# CO2_Sensor_Unit_board.net
KiCad netlist of a schematic drawn in Altium Designer
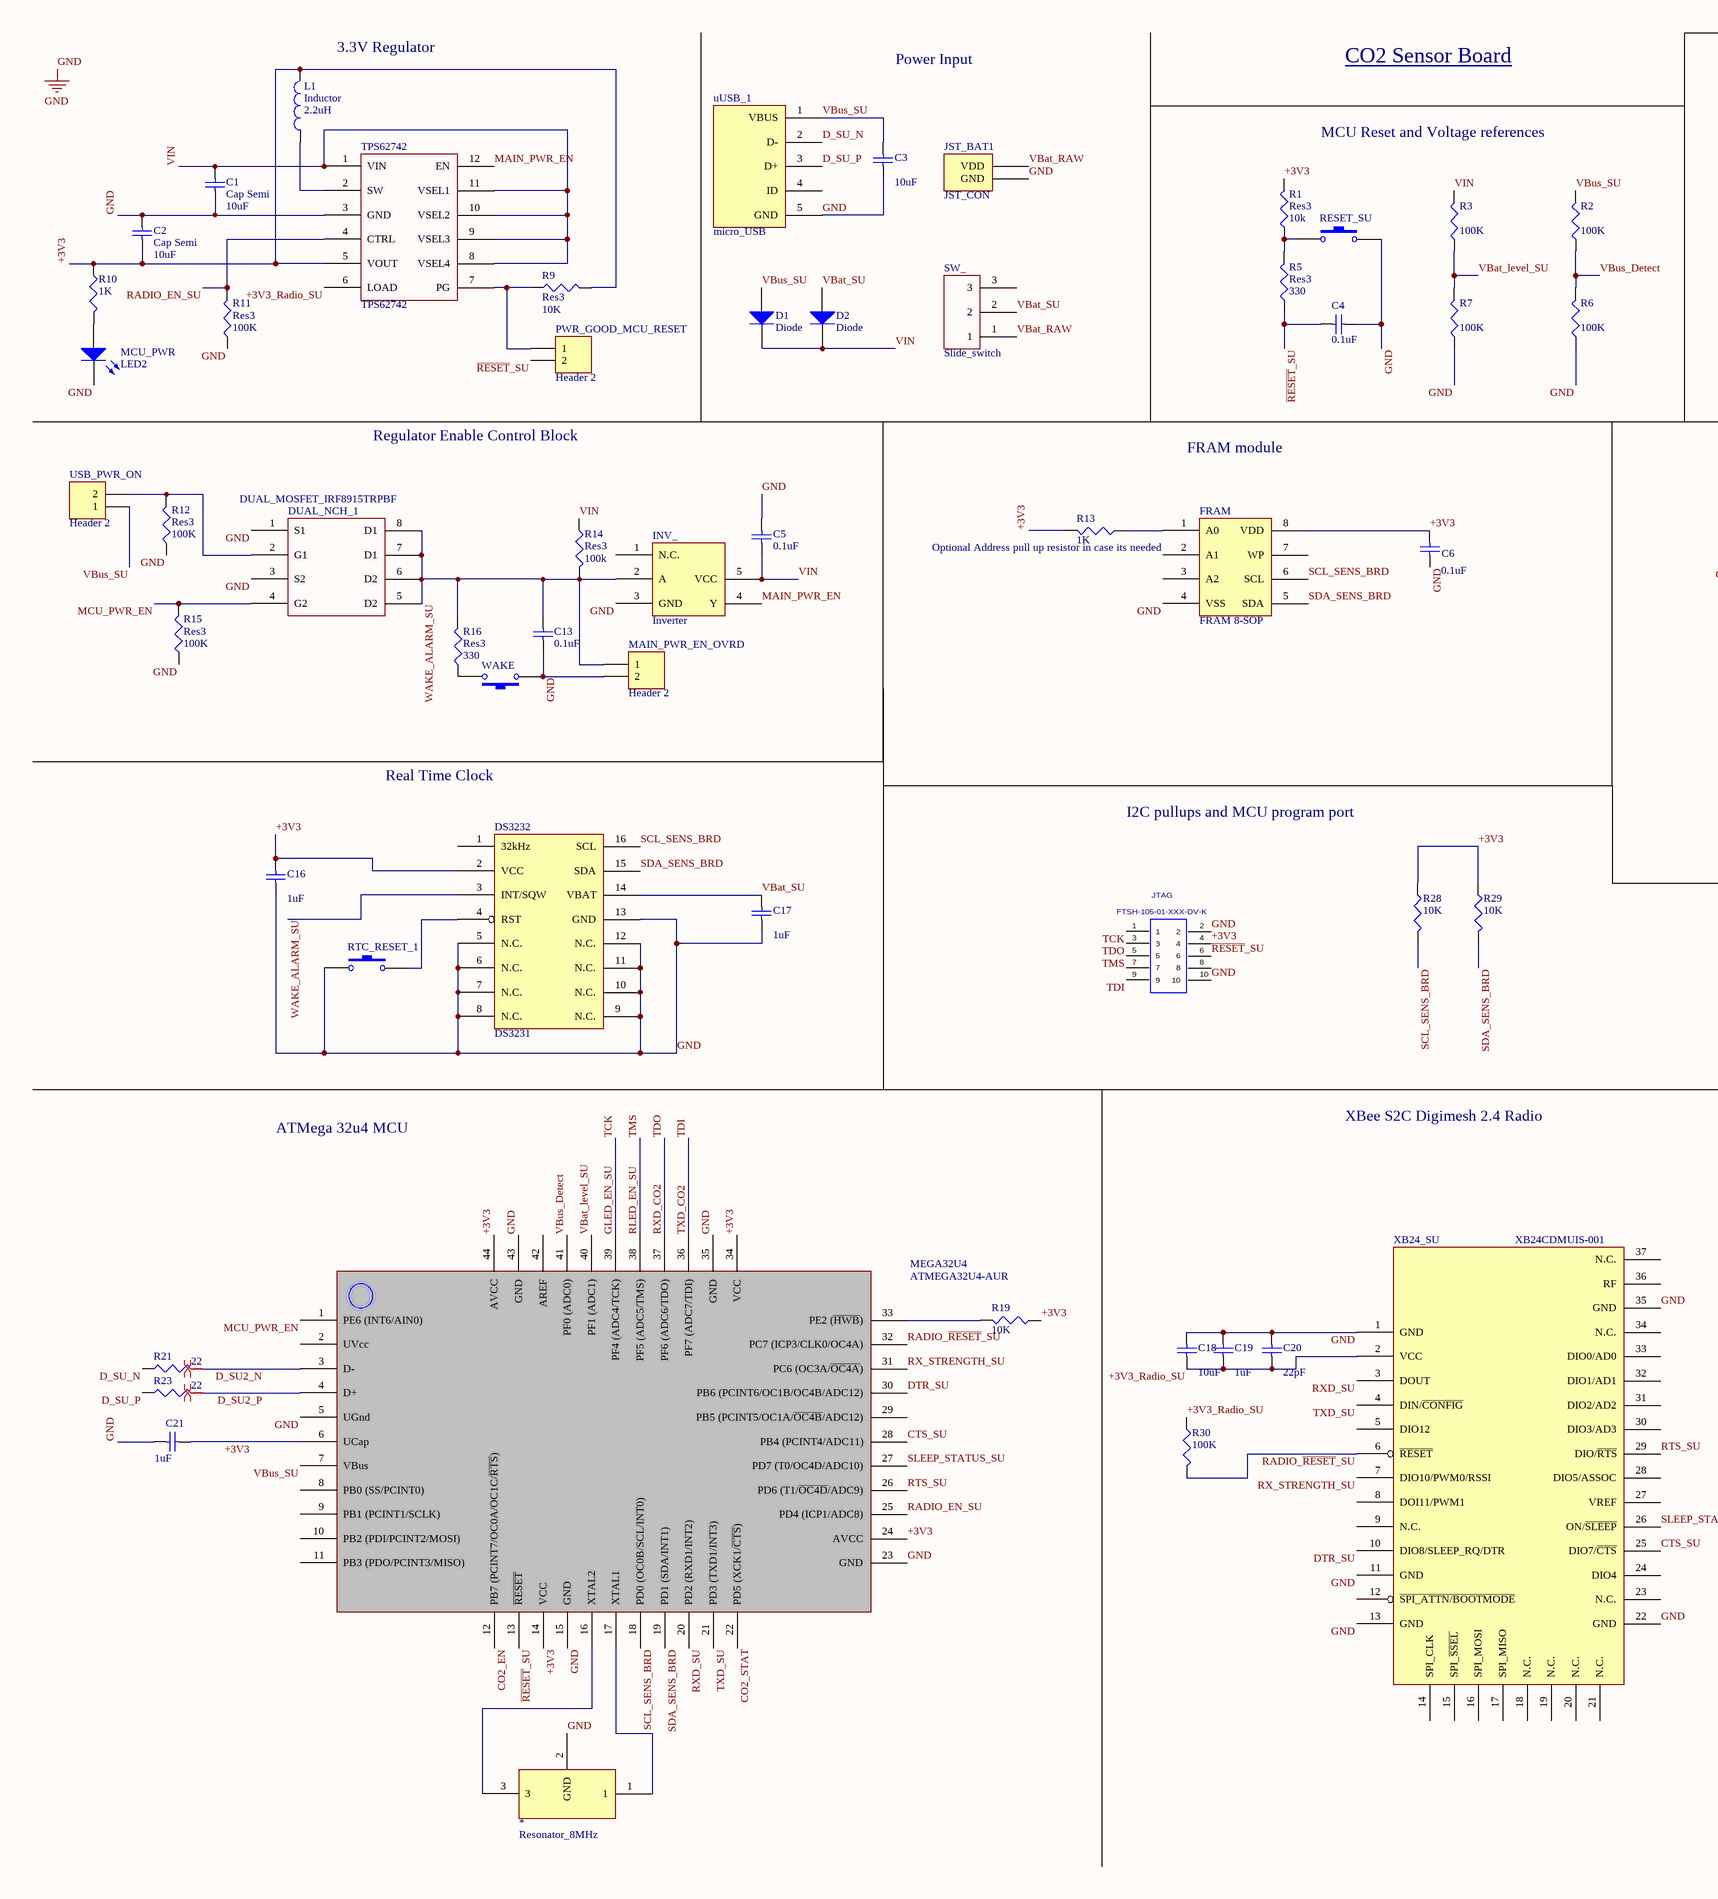
[diagram p0: CO2_Sensor_Unit_board.SchDoc, left]
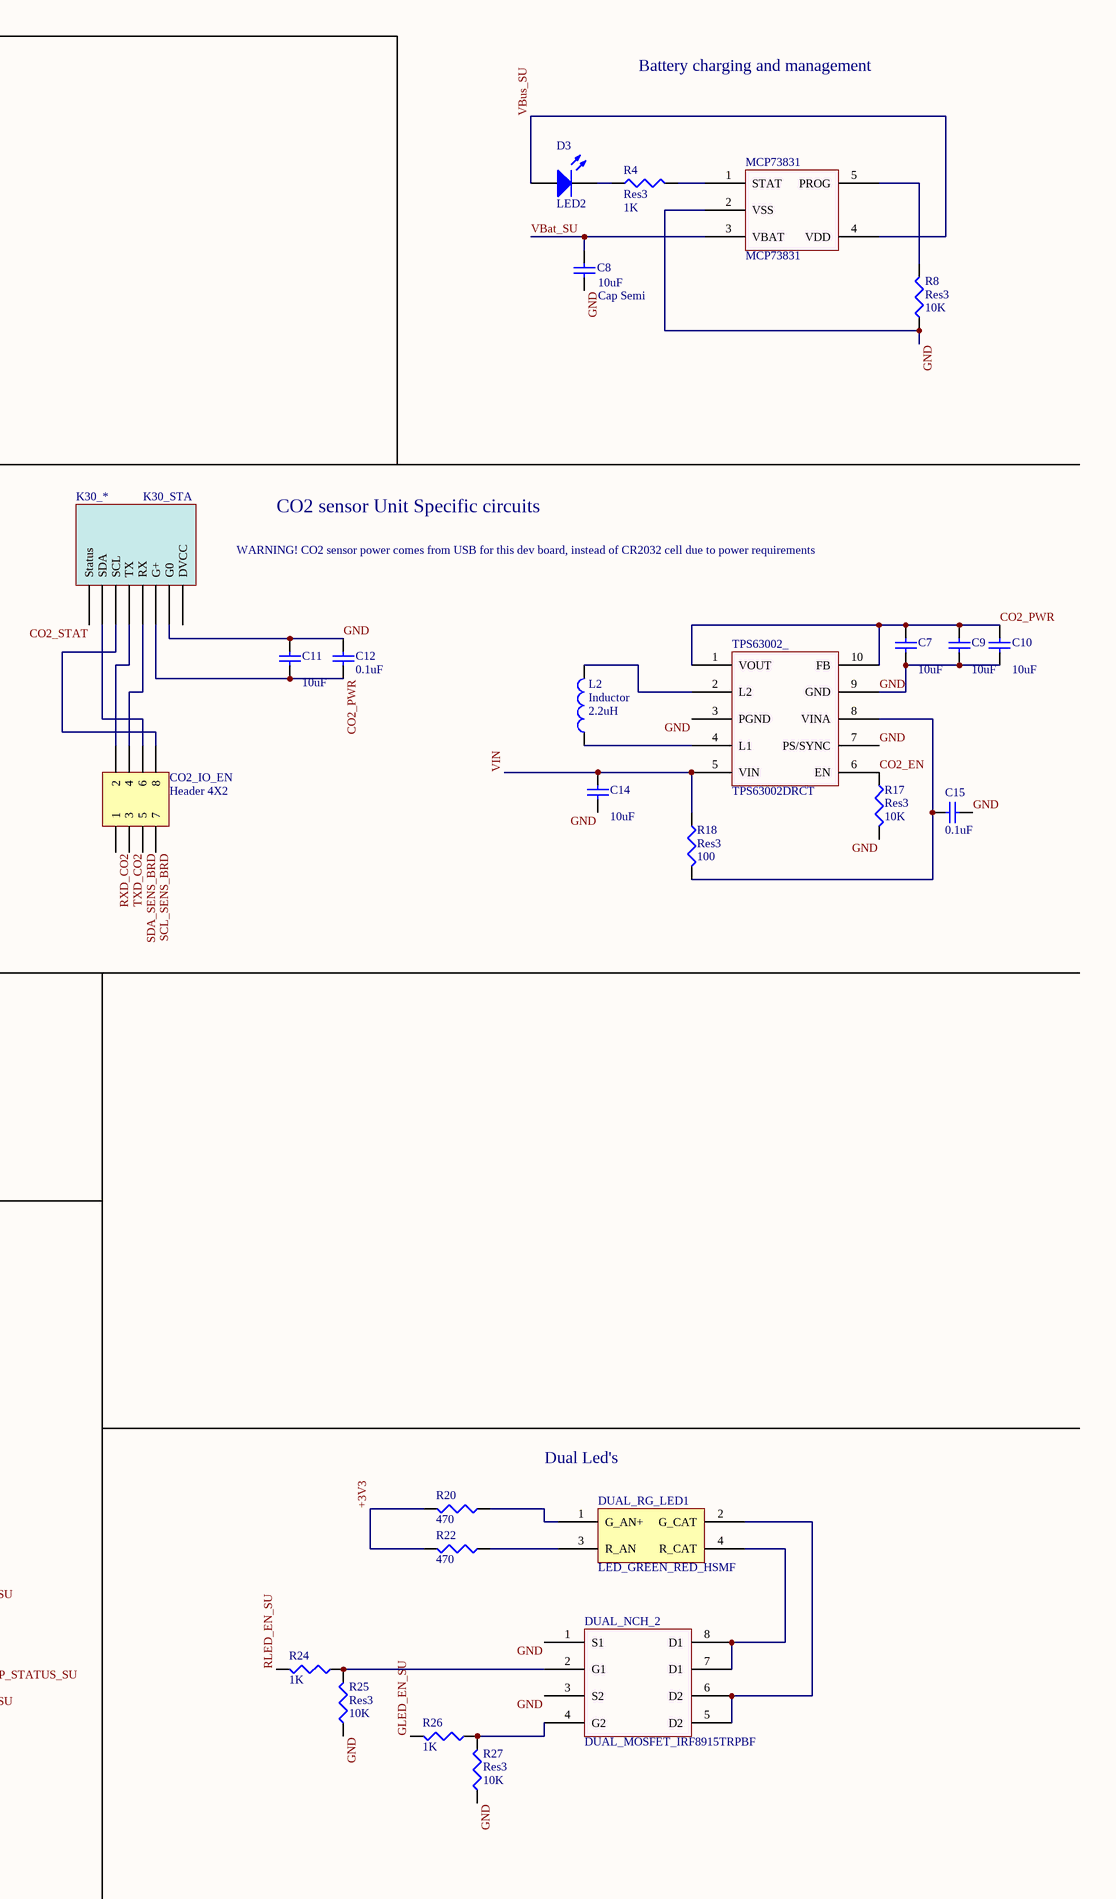
[diagram p1: CO2_Sensor_Unit_board.SchDoc, right]

(export (version "E")
  (design (tool "Eeschema 10.0.6"))
  (components
    (comp (ref "*")
      (value "Resonator_8MHz")
      (footprint "Resonator_8MHz")
      (libsource (lib "SMD_components") (part "Resonator_8MHz"))
    )
    (comp (ref "C1")
      (value "Cap Semi")
      (footprint "1608[0603]")
      (description "Capacitor (Semiconductor SIM Model)")
      (fields (field (name "ALTIUM_VALUE") "10uF") (field (name "PUBLISHER") "Altium Limited"))
      (libsource (lib "Miscellaneous Devices") (part "Cap Semi"))
    )
    (comp (ref "C2")
      (value "Cap Semi")
      (footprint "1608[0603]")
      (description "Capacitor (Semiconductor SIM Model)")
      (fields (field (name "ALTIUM_VALUE") "10uF") (field (name "PUBLISHER") "Altium Limited"))
      (libsource (lib "Miscellaneous Devices") (part "Cap Semi"))
    )
    (comp (ref "C3")
      (value "10uF")
      (footprint "1608[0603]")
      (description "Capacitor (Semiconductor SIM Model)")
      (fields (field (name "Comment") "Cap Semi") (field (name "PUBLISHER") "Altium Limited"))
      (libsource (lib "Miscellaneous Devices") (part "Cap Semi"))
    )
    (comp (ref "C4")
      (value "0.1uF")
      (footprint "C0805")
      (description "Capacitor (Semiconductor SIM Model)")
      (fields (field (name "Comment") "Cap Semi") (field (name "PUBLISHER") "Altium Limited"))
      (libsource (lib "Miscellaneous Devices") (part "Cap Semi"))
    )
    (comp (ref "C5")
      (value "0.1uF")
      (footprint "C0805")
      (description "Capacitor (Semiconductor SIM Model)")
      (fields (field (name "Comment") "Cap Semi") (field (name "PUBLISHER") "Altium Limited"))
      (libsource (lib "Miscellaneous Devices") (part "Cap Semi"))
    )
    (comp (ref "C6")
      (value "0.1uF")
      (footprint "C0805")
      (description "Capacitor (Semiconductor SIM Model)")
      (fields (field (name "Comment") "Cap Semi") (field (name "PUBLISHER") "Altium Limited"))
      (libsource (lib "Miscellaneous Devices") (part "Cap Semi"))
    )
    (comp (ref "C7")
      (value "10uF")
      (footprint "1608[0603]")
      (description "Capacitor (Semiconductor SIM Model)")
      (fields (field (name "Comment") "Cap Semi") (field (name "PUBLISHER") "Altium Limited"))
      (libsource (lib "Miscellaneous Devices") (part "Cap Semi"))
    )
    (comp (ref "C8")
      (value "Cap Semi")
      (footprint "1608[0603]")
      (description "Capacitor (Semiconductor SIM Model)")
      (fields (field (name "ALTIUM_VALUE") "10uF") (field (name "PUBLISHER") "Altium Limited"))
      (libsource (lib "Miscellaneous Devices") (part "Cap Semi"))
    )
    (comp (ref "C9")
      (value "10uF")
      (footprint "1608[0603]")
      (description "Capacitor (Semiconductor SIM Model)")
      (fields (field (name "Comment") "Cap Semi") (field (name "PUBLISHER") "Altium Limited"))
      (libsource (lib "Miscellaneous Devices") (part "Cap Semi"))
    )
    (comp (ref "C10")
      (value "10uF")
      (footprint "1608[0603]")
      (description "Capacitor (Semiconductor SIM Model)")
      (fields (field (name "Comment") "Cap Semi") (field (name "PUBLISHER") "Altium Limited"))
      (libsource (lib "Miscellaneous Devices") (part "Cap Semi"))
    )
    (comp (ref "C11")
      (value "10uF")
      (footprint "1608[0603]")
      (description "Capacitor (Semiconductor SIM Model)")
      (fields (field (name "Comment") "Cap Semi") (field (name "PUBLISHER") "Altium Limited"))
      (libsource (lib "Miscellaneous Devices") (part "Cap Semi"))
    )
    (comp (ref "C12")
      (value "0.1uF")
      (footprint "C0805")
      (description "Capacitor (Semiconductor SIM Model)")
      (fields (field (name "Comment") "Cap Semi") (field (name "PUBLISHER") "Altium Limited"))
      (libsource (lib "Miscellaneous Devices") (part "Cap Semi"))
    )
    (comp (ref "C13")
      (value "0.1uF")
      (footprint "C0805")
      (description "Capacitor (Semiconductor SIM Model)")
      (fields (field (name "Comment") "Cap Semi") (field (name "PUBLISHER") "Altium Limited"))
      (libsource (lib "Miscellaneous Devices") (part "Cap Semi"))
    )
    (comp (ref "C14")
      (value "10uF")
      (footprint "1608[0603]")
      (description "Capacitor (Semiconductor SIM Model)")
      (fields (field (name "Comment") "Cap Semi") (field (name "PUBLISHER") "Altium Limited"))
      (libsource (lib "Miscellaneous Devices") (part "Cap Semi"))
    )
    (comp (ref "C15")
      (value "0.1uF")
      (footprint "C0805")
      (description "Capacitor (Semiconductor SIM Model)")
      (fields (field (name "Comment") "Cap Semi") (field (name "PUBLISHER") "Altium Limited"))
      (libsource (lib "Miscellaneous Devices") (part "Cap Semi"))
    )
    (comp (ref "C16")
      (value "1uF")
      (footprint "C0805")
      (description "Capacitor (Semiconductor SIM Model)")
      (fields (field (name "Comment") "Cap Semi") (field (name "PUBLISHER") "Altium Limited"))
      (libsource (lib "Miscellaneous Devices") (part "Cap Semi"))
    )
    (comp (ref "C17")
      (value "1uF")
      (footprint "C0805")
      (description "Capacitor (Semiconductor SIM Model)")
      (fields (field (name "Comment") "Cap Semi") (field (name "PUBLISHER") "Altium Limited"))
      (libsource (lib "Miscellaneous Devices") (part "Cap Semi"))
    )
    (comp (ref "C18")
      (value "10uF")
      (footprint "1608[0603]")
      (description "Capacitor (Semiconductor SIM Model)")
      (fields (field (name "Comment") "Cap Semi") (field (name "PUBLISHER") "Altium Limited"))
      (libsource (lib "Miscellaneous Devices") (part "Cap Semi"))
    )
    (comp (ref "C19")
      (value "1uF")
      (footprint "C0805")
      (description "Capacitor (Semiconductor SIM Model)")
      (fields (field (name "Comment") "Cap Semi") (field (name "PUBLISHER") "Altium Limited"))
      (libsource (lib "Miscellaneous Devices") (part "Cap Semi"))
    )
    (comp (ref "C20")
      (value "22pF")
      (footprint "1608[0603]")
      (description "Capacitor (Semiconductor SIM Model)")
      (fields (field (name "Comment") "Cap Semi") (field (name "PUBLISHER") "Altium Limited"))
      (libsource (lib "Miscellaneous Devices") (part "Cap Semi"))
    )
    (comp (ref "C21")
      (value "1uF")
      (footprint "C0805")
      (description "Capacitor (Semiconductor SIM Model)")
      (fields (field (name "Comment") "Cap Semi") (field (name "PUBLISHER") "Altium Limited"))
      (libsource (lib "Miscellaneous Devices") (part "Cap Semi"))
    )
    (comp (ref "CO2_IO_EN")
      (value "Header 4X2")
      (footprint "HDR2X4")
      (description "Header, 4-Pin, Dual row")
      (fields (field (name "PUBLISHER") "Altium Limited"))
      (libsource (lib "Miscellaneous Connectors") (part "Header 4X2"))
    )
    (comp (ref "D1")
      (value "Diode")
      (footprint "DO-214AC")
      (description "Default Diode")
      (fields (field (name "PUBLISHER") "Altium Limited"))
      (libsource (lib "Miscellaneous Devices") (part "Diode"))
    )
    (comp (ref "D2")
      (value "Diode")
      (footprint "DO-214AC")
      (description "Default Diode")
      (fields (field (name "PUBLISHER") "Altium Limited"))
      (libsource (lib "Miscellaneous Devices") (part "Diode"))
    )
    (comp (ref "D3")
      (value "LED2")
      (footprint "LED_Single_Orange")
      (description "Typical RED, GREEN, YELLOW, AMBER GaAs LED")
      (fields (field (name "PUBLISHER") "Altium Limited"))
      (libsource (lib "Miscellaneous Devices") (part "LED2"))
    )
    (comp (ref "DS3232")
      (value "DS3231")
      (footprint "16 SO")
      (libsource (lib "SMD_components") (part "DS3231"))
    )
    (comp (ref "DUAL_NCH_1")
      (value "DUAL_MOSFET_IRF8915TRPBF")
      (footprint "SOP-8")
      (libsource (lib "SMD_components") (part "DUAL_MOSFET_IRF8915TRPBF"))
    )
    (comp (ref "DUAL_NCH_2")
      (value "DUAL_MOSFET_IRF8915TRPBF")
      (footprint "SOP-8")
      (libsource (lib "SMD_components") (part "DUAL_MOSFET_IRF8915TRPBF"))
    )
    (comp (ref "DUAL_RG_LED1")
      (value "LED_GREEN_RED_HSMF")
      (footprint "LED4")
      (libsource (lib "SMD_components") (part "LED_GREEN_RED_HSMF"))
    )
    (comp (ref "FRAM")
      (value "FRAM 8-SOP")
      (footprint "SOP-8")
      (libsource (lib "SMD_components") (part "FRAM 8-SOP"))
    )
    (comp (ref "INV_")
      (value "Inverter")
      (footprint "SOT-23")
      (libsource (lib "SMD_components") (part "SN74LVC1GU04"))
    )
    (comp (ref "JST_BAT1")
      (value "JST_CON")
      (footprint "JST_CONN_SMT_Vertical")
      (libsource (lib "Parts_Schematic") (part "JST_CON"))
    )
    (comp (ref "JTAG")
      (value "FTSH-105-01-XXX-DV-K")
      (footprint "FTSH-105-01-XXX-DV-K")
      (description "TERMINAL STRIP, .050\"(1.27mm) PITCH, 10 PINS, KEYED")
      (fields (field (name "MANUFACTURER") "SAMTEC") (field (name "CREATED") "November 30, 2016 - Wendy Xin"))
      (libsource (lib "FTSH-105-01-XXX-DV-K") (part "FTSH-105-01-XXX-DV-K"))
    )
    (comp (ref "K30_*")
      (value "K30_STA")
      (footprint "K30_STA")
      (libsource (lib "Schematic_Library_DaughterBoard") (part "K30_STA"))
    )
    (comp (ref "L1")
      (value "Inductor")
      (footprint "2.2uH_Inductor")
      (fields (field (name "ALTIUM_VALUE") "2.2uH") (field (name "PUBLISHER") "Altium Limited"))
      (libsource (lib "Miscellaneous Devices") (part "Inductor"))
    )
    (comp (ref "L2")
      (value "Inductor")
      (footprint "2.2uH_Inductor")
      (fields (field (name "ALTIUM_VALUE") "2.2uH") (field (name "PUBLISHER") "Altium Limited"))
      (libsource (lib "Miscellaneous Devices") (part "Inductor"))
    )
    (comp (ref "MAIN_PWR_EN_OVRD")
      (value "Header 2")
      (footprint "HDR1X2")
      (description "Header, 2-Pin")
      (fields (field (name "PUBLISHER") "Altium Limited"))
      (libsource (lib "") (part "Header 2_1"))
    )
    (comp (ref "MCP73831")
      (value "MCP73831")
      (footprint "SOT-23")
      (libsource (lib "SMD_components") (part "MCP73831"))
    )
    (comp (ref "MCU_PWR")
      (value "LED2")
      (footprint "LED_Single_Orange")
      (description "Typical RED, GREEN, YELLOW, AMBER GaAs LED")
      (fields (field (name "PUBLISHER") "Altium Limited"))
      (libsource (lib "Miscellaneous Devices") (part "LED2"))
    )
    (comp (ref "MEGA32U4")
      (value "ATMEGA32U4-AUR")
      (footprint "Quad44")
      (libsource (lib "SMD_components") (part "ATMEGA32U4-AUR"))
    )
    (comp (ref "PWR_GOOD_MCU_RESET")
      (value "Header 2")
      (footprint "SMD_Jumper")
      (description "Header, 2-Pin")
      (fields (field (name "PUBLISHER") "Altium Limited"))
      (libsource (lib "") (part "Header 2_1"))
    )
    (comp (ref "R1")
      (value "Res3")
      (footprint "6-0805_N")
      (description "Resistor")
      (fields (field (name "ALTIUM_VALUE") "10k") (field (name "PUBLISHER") "Altium Limited"))
      (libsource (lib "Miscellaneous Devices") (part "Res3"))
    )
    (comp (ref "R2")
      (value "100K")
      (footprint "6-0805_N")
      (description "Resistor")
      (fields (field (name "Comment") "Res3") (field (name "PUBLISHER") "Altium Limited"))
      (libsource (lib "Miscellaneous Devices") (part "Res3"))
    )
    (comp (ref "R3")
      (value "100K")
      (footprint "6-0805_N")
      (description "Resistor")
      (fields (field (name "Comment") "Res3") (field (name "PUBLISHER") "Altium Limited"))
      (libsource (lib "Miscellaneous Devices") (part "Res3"))
    )
    (comp (ref "R4")
      (value "Res3")
      (footprint "6-0805_N")
      (description "Resistor")
      (fields (field (name "ALTIUM_VALUE") "1K") (field (name "PUBLISHER") "Altium Limited"))
      (libsource (lib "Miscellaneous Devices") (part "Res3"))
    )
    (comp (ref "R5")
      (value "Res3")
      (footprint "6-0805_N")
      (description "Resistor")
      (fields (field (name "ALTIUM_VALUE") "330") (field (name "PUBLISHER") "Altium Limited"))
      (libsource (lib "Miscellaneous Devices") (part "Res3"))
    )
    (comp (ref "R6")
      (value "100K")
      (footprint "6-0805_N")
      (description "Resistor")
      (fields (field (name "Comment") "Res3") (field (name "PUBLISHER") "Altium Limited"))
      (libsource (lib "Miscellaneous Devices") (part "Res3"))
    )
    (comp (ref "R7")
      (value "100K")
      (footprint "6-0805_N")
      (description "Resistor")
      (fields (field (name "Comment") "Res3") (field (name "PUBLISHER") "Altium Limited"))
      (libsource (lib "Miscellaneous Devices") (part "Res3"))
    )
    (comp (ref "R8")
      (value "Res3")
      (footprint "6-0805_N")
      (description "Resistor")
      (fields (field (name "ALTIUM_VALUE") "10K") (field (name "PUBLISHER") "Altium Limited"))
      (libsource (lib "Miscellaneous Devices") (part "Res3"))
    )
    (comp (ref "R9")
      (value "Res3")
      (footprint "6-0805_N")
      (description "Resistor")
      (fields (field (name "ALTIUM_VALUE") "10K") (field (name "PUBLISHER") "Altium Limited"))
      (libsource (lib "Miscellaneous Devices") (part "Res3"))
    )
    (comp (ref "R10")
      (value "1K")
      (footprint "6-0805_N")
      (description "Resistor")
      (fields (field (name "Comment") "Res3") (field (name "PUBLISHER") "Altium Limited"))
      (libsource (lib "Miscellaneous Devices") (part "Res3"))
    )
    (comp (ref "R11")
      (value "Res3")
      (footprint "6-0805_N")
      (description "Resistor")
      (fields (field (name "ALTIUM_VALUE") "100K") (field (name "PUBLISHER") "Altium Limited"))
      (libsource (lib "Miscellaneous Devices") (part "Res3"))
    )
    (comp (ref "R12")
      (value "Res3")
      (footprint "6-0805_N")
      (description "Resistor")
      (fields (field (name "ALTIUM_VALUE") "100K") (field (name "PUBLISHER") "Altium Limited"))
      (libsource (lib "Miscellaneous Devices") (part "Res3"))
    )
    (comp (ref "R13")
      (value "1K")
      (footprint "6-0805_N")
      (description "Resistor")
      (fields (field (name "Comment") "Res3") (field (name "PUBLISHER") "Altium Limited"))
      (libsource (lib "Miscellaneous Devices") (part "Res3"))
    )
    (comp (ref "R14")
      (value "Res3")
      (footprint "6-0805_N")
      (description "Resistor")
      (fields (field (name "ALTIUM_VALUE") "100k") (field (name "PUBLISHER") "Altium Limited"))
      (libsource (lib "Miscellaneous Devices") (part "Res3"))
    )
    (comp (ref "R15")
      (value "Res3")
      (footprint "6-0805_N")
      (description "Resistor")
      (fields (field (name "ALTIUM_VALUE") "100K") (field (name "PUBLISHER") "Altium Limited"))
      (libsource (lib "Miscellaneous Devices") (part "Res3"))
    )
    (comp (ref "R16")
      (value "Res3")
      (footprint "6-0805_N")
      (description "Resistor")
      (fields (field (name "ALTIUM_VALUE") "330") (field (name "PUBLISHER") "Altium Limited"))
      (libsource (lib "Miscellaneous Devices") (part "Res3"))
    )
    (comp (ref "R17")
      (value "Res3")
      (footprint "6-0805_N")
      (description "Resistor")
      (fields (field (name "ALTIUM_VALUE") "10K") (field (name "PUBLISHER") "Altium Limited"))
      (libsource (lib "Miscellaneous Devices") (part "Res3"))
    )
    (comp (ref "R18")
      (value "Res3")
      (footprint "6-0805_N")
      (description "Resistor")
      (fields (field (name "ALTIUM_VALUE") "100") (field (name "PUBLISHER") "Altium Limited"))
      (libsource (lib "Miscellaneous Devices") (part "Res3"))
    )
    (comp (ref "R19")
      (value "10K")
      (footprint "6-0805_N")
      (description "Resistor")
      (fields (field (name "Comment") "Res3") (field (name "PUBLISHER") "Altium Limited"))
      (libsource (lib "Miscellaneous Devices") (part "Res3"))
    )
    (comp (ref "R20")
      (value "470")
      (footprint "6-0805_N")
      (description "Resistor")
      (fields (field (name "Comment") "Res3") (field (name "PUBLISHER") "Altium Limited"))
      (libsource (lib "Miscellaneous Devices") (part "Res3"))
    )
    (comp (ref "R21")
      (value "22")
      (footprint "6-0805_N")
      (description "Resistor")
      (fields (field (name "Comment") "Res3") (field (name "PUBLISHER") "Altium Limited"))
      (libsource (lib "Miscellaneous Devices") (part "Res3"))
    )
    (comp (ref "R22")
      (value "470")
      (footprint "6-0805_N")
      (description "Resistor")
      (fields (field (name "Comment") "Res3") (field (name "PUBLISHER") "Altium Limited"))
      (libsource (lib "Miscellaneous Devices") (part "Res3"))
    )
    (comp (ref "R23")
      (value "22")
      (footprint "6-0805_N")
      (description "Resistor")
      (fields (field (name "Comment") "Res3") (field (name "PUBLISHER") "Altium Limited"))
      (libsource (lib "Miscellaneous Devices") (part "Res3"))
    )
    (comp (ref "R24")
      (value "1K")
      (footprint "6-0805_N")
      (description "Resistor")
      (fields (field (name "Comment") "Res3") (field (name "PUBLISHER") "Altium Limited"))
      (libsource (lib "Miscellaneous Devices") (part "Res3"))
    )
    (comp (ref "R25")
      (value "Res3")
      (footprint "6-0805_N")
      (description "Resistor")
      (fields (field (name "ALTIUM_VALUE") "10K") (field (name "PUBLISHER") "Altium Limited"))
      (libsource (lib "Miscellaneous Devices") (part "Res3"))
    )
    (comp (ref "R26")
      (value "1K")
      (footprint "6-0805_N")
      (description "Resistor")
      (fields (field (name "Comment") "Res3") (field (name "PUBLISHER") "Altium Limited"))
      (libsource (lib "Miscellaneous Devices") (part "Res3"))
    )
    (comp (ref "R27")
      (value "Res3")
      (footprint "6-0805_N")
      (description "Resistor")
      (fields (field (name "ALTIUM_VALUE") "10K") (field (name "PUBLISHER") "Altium Limited"))
      (libsource (lib "Miscellaneous Devices") (part "Res3"))
    )
    (comp (ref "R28")
      (value "10K")
      (footprint "6-0805_N")
      (description "Resistor")
      (fields (field (name "Comment") "Res3") (field (name "PUBLISHER") "Altium Limited"))
      (libsource (lib "Miscellaneous Devices") (part "Res3"))
    )
    (comp (ref "R29")
      (value "10K")
      (footprint "6-0805_N")
      (description "Resistor")
      (fields (field (name "Comment") "Res3") (field (name "PUBLISHER") "Altium Limited"))
      (libsource (lib "Miscellaneous Devices") (part "Res3"))
    )
    (comp (ref "R30")
      (value "100K")
      (footprint "6-0805_N")
      (description "Resistor")
      (fields (field (name "Comment") "Res3") (field (name "PUBLISHER") "Altium Limited"))
      (libsource (lib "Miscellaneous Devices") (part "Res3"))
    )
    (comp (ref "RESET_SU")
      (value "SW-PB")
      (footprint "SW_TACTILE")
      (description "Switch")
      (fields (field (name "PUBLISHER") "Altium Limited"))
      (libsource (lib "Miscellaneous Devices") (part "SW-PB"))
    )
    (comp (ref "RTC_RESET_1")
      (value "SW-PB")
      (footprint "SW_TACTILE")
      (description "Switch")
      (fields (field (name "PUBLISHER") "Altium Limited"))
      (libsource (lib "Miscellaneous Devices") (part "SW-PB"))
    )
    (comp (ref "SW_")
      (value "Slide_switch")
      (footprint "Slide_SW")
      (libsource (lib "SMD_components") (part "Slide_switch"))
    )
    (comp (ref "TPS62742")
      (value "TPS62742")
      (footprint "WSON12 - small")
      (libsource (lib "SMD_components") (part "TPS62742"))
    )
    (comp (ref "TPS63002_")
      (value "TPS63002DRCT")
      (footprint "SON10 - small")
      (libsource (lib "SMD_components") (part "TPS63001DRCT"))
    )
    (comp (ref "USB_PWR_ON")
      (value "Header 2")
      (footprint "HDR1X2")
      (description "Header, 2-Pin")
      (fields (field (name "PUBLISHER") "Altium Limited"))
      (libsource (lib "Miscellaneous Connectors") (part "Header 2"))
    )
    (comp (ref "uUSB_1")
      (value "micro_USB")
      (footprint "MicroUSB_CONN")
      (libsource (lib "SMD_components") (part "micro_USB"))
    )
    (comp (ref "WAKE")
      (value "SW-PB")
      (footprint "SW_TACTILE")
      (description "Switch")
      (fields (field (name "PUBLISHER") "Altium Limited"))
      (libsource (lib "Miscellaneous Devices") (part "SW-PB"))
    )
    (comp (ref "XB24_SU")
      (value "XB24CDMUIS-001")
      (footprint "XB24_RADIO")
      (libsource (lib "SMD_components") (part "XB24CDMUIS-001"))
    )
  )
  (nets
    (net (code "1") (name "/+3V3") (class "Default")
      (node (ref "C16") (pin "2") (pinfunction "2_2") (pintype "passive"))
      (node (ref "C2") (pin "2") (pinfunction "2_2") (pintype "passive"))
      (node (ref "C21") (pin "2") (pinfunction "2_2") (pintype "passive"))
      (node (ref "C6") (pin "2") (pinfunction "2_2") (pintype "passive"))
      (node (ref "DS3232") (pin "2") (pinfunction "VCC_2") (pintype "passive"))
      (node (ref "FRAM") (pin "8") (pinfunction "VDD_8") (pintype "passive"))
      (node (ref "JTAG") (pin "4") (pinfunction "4_4") (pintype "passive"))
      (node (ref "L1") (pin "2") (pinfunction "2_2") (pintype "passive"))
      (node (ref "MEGA32U4") (pin "14") (pinfunction "VCC_14") (pintype "passive"))
      (node (ref "MEGA32U4") (pin "24") (pinfunction "AVCC_24") (pintype "passive"))
      (node (ref "MEGA32U4") (pin "34") (pinfunction "VCC_34") (pintype "passive"))
      (node (ref "MEGA32U4") (pin "44") (pinfunction "AVCC_44") (pintype "passive"))
      (node (ref "MEGA32U4") (pin "6") (pinfunction "UCap_6") (pintype "passive"))
      (node (ref "R1") (pin "2") (pinfunction "2_2") (pintype "passive"))
      (node (ref "R10") (pin "1") (pinfunction "1_1") (pintype "passive"))
      (node (ref "R13") (pin "2") (pinfunction "2_2") (pintype "passive"))
      (node (ref "R19") (pin "1") (pinfunction "1_1") (pintype "passive"))
      (node (ref "R20") (pin "2") (pinfunction "2_2") (pintype "passive"))
      (node (ref "R22") (pin "2") (pinfunction "2_2") (pintype "passive"))
      (node (ref "R28") (pin "1") (pinfunction "1_1") (pintype "passive"))
      (node (ref "R29") (pin "1") (pinfunction "1_1") (pintype "passive"))
      (node (ref "R9") (pin "2") (pinfunction "2_2") (pintype "passive"))
      (node (ref "TPS62742") (pin "5") (pinfunction "VOUT_5") (pintype "passive"))
    )
    (net (code "2") (name "/+3V3_Radio_SU") (class "Default")
      (node (ref "C18") (pin "1") (pinfunction "1_1") (pintype "passive"))
      (node (ref "C19") (pin "1") (pinfunction "1_1") (pintype "passive"))
      (node (ref "C20") (pin "1") (pinfunction "1_1") (pintype "passive"))
      (node (ref "R30") (pin "1") (pinfunction "1_1") (pintype "passive"))
      (node (ref "TPS62742") (pin "6") (pinfunction "LOAD_6") (pintype "passive"))
      (node (ref "XB24_SU") (pin "2") (pinfunction "VCC_2") (pintype "passive"))
    )
    (net (code "3") (name "/CO2_EN") (class "Default")
      (node (ref "MEGA32U4") (pin "12") (pinfunction "PB7_(PCINT7/OC0A/OC1C/~{RTS})_12") (pintype "passive"))
      (node (ref "R17") (pin "1") (pinfunction "1_1") (pintype "passive"))
      (node (ref "TPS63002_") (pin "6") (pinfunction "EN_6") (pintype "passive"))
    )
    (net (code "4") (name "/CO2_PWR") (class "Default")
      (node (ref "C10") (pin "1") (pinfunction "1_1") (pintype "passive"))
      (node (ref "C11") (pin "1") (pinfunction "1_1") (pintype "passive"))
      (node (ref "C12") (pin "1") (pinfunction "1_1") (pintype "passive"))
      (node (ref "C7") (pin "1") (pinfunction "1_1") (pintype "passive"))
      (node (ref "C9") (pin "1") (pinfunction "1_1") (pintype "passive"))
      (node (ref "K30_*") (pin "6") (pinfunction "G+_6") (pintype "passive"))
      (node (ref "TPS63002_") (pin "1") (pinfunction "VOUT_1") (pintype "passive"))
      (node (ref "TPS63002_") (pin "10") (pinfunction "FB_10") (pintype "passive"))
    )
    (net (code "5") (name "/CO2_STAT") (class "Default")
      (node (ref "K30_*") (pin "1") (pinfunction "Status_1") (pintype "passive"))
      (node (ref "MEGA32U4") (pin "22") (pinfunction "PD5_(XCK1/~{CTS})_22") (pintype "passive"))
    )
    (net (code "6") (name "/CTS_SU") (class "Default")
      (node (ref "MEGA32U4") (pin "28") (pinfunction "PB4_(PCINT4/ADC11)_28") (pintype "passive"))
      (node (ref "XB24_SU") (pin "25") (pinfunction "DIO7/~{CTS}_25") (pintype "passive"))
    )
    (net (code "7") (name "/DTR_SU") (class "Default")
      (node (ref "MEGA32U4") (pin "30") (pinfunction "PB6_(PCINT6/OC1B/OC4B/ADC12)_30") (pintype "passive"))
      (node (ref "XB24_SU") (pin "10") (pinfunction "DIO8/SLEEP_RQ/DTR_10") (pintype "passive"))
    )
    (net (code "8") (name "/D_SU2_N") (class "Default")
      (node (ref "MEGA32U4") (pin "3") (pinfunction "D-_3") (pintype "passive"))
      (node (ref "R21") (pin "2") (pinfunction "2_2") (pintype "passive"))
    )
    (net (code "9") (name "/D_SU2_P") (class "Default")
      (node (ref "MEGA32U4") (pin "4") (pinfunction "D+_4") (pintype "passive"))
      (node (ref "R23") (pin "2") (pinfunction "2_2") (pintype "passive"))
    )
    (net (code "10") (name "/D_SU_N") (class "Default")
      (node (ref "R21") (pin "1") (pinfunction "1_1") (pintype "passive"))
      (node (ref "uUSB_1") (pin "2") (pinfunction "D-_2") (pintype "passive"))
    )
    (net (code "11") (name "/D_SU_P") (class "Default")
      (node (ref "R23") (pin "1") (pinfunction "1_1") (pintype "passive"))
      (node (ref "uUSB_1") (pin "3") (pinfunction "D+_3") (pintype "passive"))
    )
    (net (code "12") (name "/GLED_EN_SU") (class "Default")
      (node (ref "JTAG") (pin "1") (pinfunction "1_1") (pintype "passive"))
      (node (ref "MEGA32U4") (pin "39") (pinfunction "PF4_(ADC4/TCK)_39") (pintype "passive"))
      (node (ref "R26") (pin "2") (pinfunction "2_2") (pintype "passive"))
    )
    (net (code "13") (name "/MAIN_PWR_EN") (class "Default")
      (node (ref "INV_") (pin "4") (pinfunction "Y_4") (pintype "passive"))
      (node (ref "TPS62742") (pin "12") (pinfunction "EN_12") (pintype "passive"))
    )
    (net (code "14") (name "/MCU_PWR_EN") (class "Default")
      (node (ref "DUAL_NCH_1") (pin "4") (pinfunction "G2_4") (pintype "passive"))
      (node (ref "MEGA32U4") (pin "1") (pinfunction "PE6_(INT6/AIN0)_1") (pintype "passive"))
      (node (ref "R15") (pin "2") (pinfunction "2_2") (pintype "passive"))
    )
    (net (code "15") (name "/RADIO_EN_SU") (class "Default")
      (node (ref "MEGA32U4") (pin "25") (pinfunction "PD4_(ICP1/ADC8)_25") (pintype "passive"))
      (node (ref "R11") (pin "2") (pinfunction "2_2") (pintype "passive"))
      (node (ref "TPS62742") (pin "4") (pinfunction "CTRL_4") (pintype "passive"))
    )
    (net (code "16") (name "/RADIO_~{RESET}_SU") (class "Default")
      (node (ref "MEGA32U4") (pin "32") (pinfunction "PC7_(ICP3/CLK0/OC4A)_32") (pintype "passive"))
      (node (ref "R30") (pin "2") (pinfunction "2_2") (pintype "passive"))
      (node (ref "XB24_SU") (pin "6") (pinfunction "~{RESET}_6") (pintype "passive"))
    )
    (net (code "17") (name "/RLED_EN_SU") (class "Default")
      (node (ref "JTAG") (pin "5") (pinfunction "5_5") (pintype "passive"))
      (node (ref "MEGA32U4") (pin "38") (pinfunction "PF5_(ADC5/TMS)_38") (pintype "passive"))
      (node (ref "R24") (pin "2") (pinfunction "2_2") (pintype "passive"))
    )
    (net (code "18") (name "/RTS_SU") (class "Default")
      (node (ref "MEGA32U4") (pin "26") (pinfunction "PD6_(T1/~{OC4D}/ADC9)_26") (pintype "passive"))
      (node (ref "XB24_SU") (pin "29") (pinfunction "DIO/~{RTS}_29") (pintype "passive"))
    )
    (net (code "19") (name "/RXD_CO2") (class "Default")
      (node (ref "CO2_IO_EN") (pin "1") (pinfunction "1_1") (pintype "passive"))
      (node (ref "JTAG") (pin "3") (pinfunction "3_3") (pintype "passive"))
      (node (ref "MEGA32U4") (pin "37") (pinfunction "PF6_(ADC6/TDO)_37") (pintype "passive"))
    )
    (net (code "20") (name "/RXD_SU") (class "Default")
      (node (ref "MEGA32U4") (pin "20") (pinfunction "PD2_(RXD1/INT2)_20") (pintype "passive"))
      (node (ref "XB24_SU") (pin "3") (pinfunction "DOUT_3") (pintype "passive"))
    )
    (net (code "21") (name "/RX_STRENGTH_SU") (class "Default")
      (node (ref "MEGA32U4") (pin "31") (pinfunction "PC6_(OC3A/~{OC4A})_31") (pintype "passive"))
      (node (ref "XB24_SU") (pin "7") (pinfunction "DIO10/PWM0/RSSI_7") (pintype "passive"))
    )
    (net (code "22") (name "/SCL_SENS_BRD") (class "Default")
      (node (ref "CO2_IO_EN") (pin "7") (pinfunction "7_7") (pintype "passive"))
      (node (ref "DS3232") (pin "16") (pinfunction "SCL_16") (pintype "passive"))
      (node (ref "FRAM") (pin "6") (pinfunction "SCL_6") (pintype "passive"))
      (node (ref "MEGA32U4") (pin "18") (pinfunction "PD0_(OC0B/SCL/INT0)_18") (pintype "passive"))
      (node (ref "R28") (pin "2") (pinfunction "2_2") (pintype "passive"))
    )
    (net (code "23") (name "/SDA_SENS_BRD") (class "Default")
      (node (ref "CO2_IO_EN") (pin "5") (pinfunction "5_5") (pintype "passive"))
      (node (ref "DS3232") (pin "15") (pinfunction "SDA_15") (pintype "passive"))
      (node (ref "FRAM") (pin "5") (pinfunction "SDA_5") (pintype "passive"))
      (node (ref "MEGA32U4") (pin "19") (pinfunction "PD1_(SDA/INT1)_19") (pintype "passive"))
      (node (ref "R29") (pin "2") (pinfunction "2_2") (pintype "passive"))
    )
    (net (code "24") (name "/SLEEP_STATUS_SU") (class "Default")
      (node (ref "MEGA32U4") (pin "27") (pinfunction "PD7_(T0/OC4D/ADC10)_27") (pintype "passive"))
      (node (ref "XB24_SU") (pin "26") (pinfunction "ON/~{SLEEP}_26") (pintype "passive"))
    )
    (net (code "25") (name "/TDI") (class "Default")
      (node (ref "CO2_IO_EN") (pin "3") (pinfunction "3_3") (pintype "passive"))
      (node (ref "JTAG") (pin "9") (pinfunction "9_9") (pintype "passive"))
      (node (ref "MEGA32U4") (pin "36") (pinfunction "PF7_(ADC7/TDI)_36") (pintype "passive"))
    )
    (net (code "26") (name "/TXD_SU") (class "Default")
      (node (ref "MEGA32U4") (pin "21") (pinfunction "PD3_(TXD1/INT3)_21") (pintype "passive"))
      (node (ref "XB24_SU") (pin "4") (pinfunction "DIN/~{CONFIG}_4") (pintype "passive"))
    )
    (net (code "27") (name "/VBat_RAW") (class "Default")
      (node (ref "JST_BAT1") (pin "2") (pinfunction "VDD_2") (pintype "passive"))
      (node (ref "SW_") (pin "1") (pinfunction "1_1") (pintype "passive"))
    )
    (net (code "28") (name "/VBat_SU") (class "Default")
      (node (ref "C17") (pin "2") (pinfunction "2_2") (pintype "passive"))
      (node (ref "C8") (pin "2") (pinfunction "2_2") (pintype "passive"))
      (node (ref "D2") (pin "1") (pinfunction "A_1") (pintype "passive"))
      (node (ref "DS3232") (pin "14") (pinfunction "VBAT_14") (pintype "passive"))
      (node (ref "MCP73831") (pin "3") (pinfunction "VBAT_3") (pintype "passive"))
      (node (ref "SW_") (pin "2") (pinfunction "2_2") (pintype "passive"))
    )
    (net (code "29") (name "/VBat_level_SU") (class "Default")
      (node (ref "MEGA32U4") (pin "40") (pinfunction "PF1_(ADC1)_40") (pintype "passive"))
      (node (ref "R3") (pin "1") (pinfunction "1_1") (pintype "passive"))
      (node (ref "R7") (pin "2") (pinfunction "2_2") (pintype "passive"))
    )
    (net (code "30") (name "/VBus_Detect") (class "Default")
      (node (ref "MEGA32U4") (pin "41") (pinfunction "PF0_(ADC0)_41") (pintype "passive"))
      (node (ref "R2") (pin "1") (pinfunction "1_1") (pintype "passive"))
      (node (ref "R6") (pin "2") (pinfunction "2_2") (pintype "passive"))
    )
    (net (code "31") (name "/VBus_SU") (class "Default")
      (node (ref "C3") (pin "2") (pinfunction "2_2") (pintype "passive"))
      (node (ref "D1") (pin "1") (pinfunction "A_1") (pintype "passive"))
      (node (ref "D3") (pin "1") (pinfunction "A_1") (pintype "passive"))
      (node (ref "MCP73831") (pin "4") (pinfunction "VDD_4") (pintype "passive"))
      (node (ref "MEGA32U4") (pin "7") (pinfunction "VBus_7") (pintype "passive"))
      (node (ref "R2") (pin "2") (pinfunction "2_2") (pintype "passive"))
      (node (ref "USB_PWR_ON") (pin "1") (pinfunction "1_1") (pintype "passive"))
      (node (ref "uUSB_1") (pin "1") (pinfunction "VBUS_1") (pintype "passive"))
    )
    (net (code "32") (name "/VIN") (class "Default")
      (node (ref "C1") (pin "2") (pinfunction "2_2") (pintype "passive"))
      (node (ref "C14") (pin "2") (pinfunction "2_2") (pintype "passive"))
      (node (ref "C5") (pin "2") (pinfunction "2_2") (pintype "passive"))
      (node (ref "D1") (pin "2") (pinfunction "K_2") (pintype "passive"))
      (node (ref "D2") (pin "2") (pinfunction "K_2") (pintype "passive"))
      (node (ref "INV_") (pin "5") (pinfunction "VCC_5") (pintype "passive"))
      (node (ref "R14") (pin "1") (pinfunction "1_1") (pintype "passive"))
      (node (ref "R18") (pin "1") (pinfunction "1_1") (pintype "passive"))
      (node (ref "R3") (pin "2") (pinfunction "2_2") (pintype "passive"))
      (node (ref "TPS62742") (pin "1") (pinfunction "VIN_1") (pintype "passive"))
      (node (ref "TPS62742") (pin "10") (pinfunction "VSEL2_10") (pintype "passive"))
      (node (ref "TPS62742") (pin "11") (pinfunction "VSEL1_11") (pintype "passive"))
      (node (ref "TPS62742") (pin "8") (pinfunction "VSEL4_8") (pintype "passive"))
      (node (ref "TPS62742") (pin "9") (pinfunction "VSEL3_9") (pintype "passive"))
      (node (ref "TPS63002_") (pin "5") (pinfunction "VIN_5") (pintype "passive"))
    )
    (net (code "33") (name "/WAKE_ALARM_SU") (class "Default")
      (node (ref "C13") (pin "1") (pinfunction "1_1") (pintype "passive"))
      (node (ref "DS3232") (pin "3") (pinfunction "INT/SQW_3") (pintype "passive"))
      (node (ref "DUAL_NCH_1") (pin "5") (pinfunction "D2_5") (pintype "passive"))
      (node (ref "DUAL_NCH_1") (pin "6") (pinfunction "D2_6") (pintype "passive"))
      (node (ref "DUAL_NCH_1") (pin "7") (pinfunction "D1_7") (pintype "passive"))
      (node (ref "DUAL_NCH_1") (pin "8") (pinfunction "D1_8") (pintype "passive"))
      (node (ref "INV_") (pin "2") (pinfunction "A_2") (pintype "passive"))
      (node (ref "MAIN_PWR_EN_OVRD") (pin "1") (pinfunction "1_1") (pintype "passive"))
      (node (ref "R14") (pin "2") (pinfunction "2_2") (pintype "passive"))
      (node (ref "R16") (pin "2") (pinfunction "2_2") (pintype "passive"))
    )
    (net (code "34") (name "/~{RESET}_SU") (class "Default")
      (node (ref "C4") (pin "2") (pinfunction "2_2") (pintype "passive"))
      (node (ref "JTAG") (pin "6") (pinfunction "6_6") (pintype "passive"))
      (node (ref "MEGA32U4") (pin "13") (pinfunction "~{RESET}_13") (pintype "passive"))
      (node (ref "PWR_GOOD_MCU_RESET") (pin "2") (pinfunction "2_2") (pintype "passive"))
      (node (ref "R5") (pin "1") (pinfunction "1_1") (pintype "passive"))
    )
    (net (code "35") (name "GND") (class "Default")
      (node (ref "*") (pin "2") (pinfunction "GND_2") (pintype "passive"))
      (node (ref "C1") (pin "1") (pinfunction "1_1") (pintype "passive"))
      (node (ref "C10") (pin "2") (pinfunction "2_2") (pintype "passive"))
      (node (ref "C11") (pin "2") (pinfunction "2_2") (pintype "passive"))
      (node (ref "C12") (pin "2") (pinfunction "2_2") (pintype "passive"))
      (node (ref "C13") (pin "2") (pinfunction "2_2") (pintype "passive"))
      (node (ref "C14") (pin "1") (pinfunction "1_1") (pintype "passive"))
      (node (ref "C15") (pin "2") (pinfunction "2_2") (pintype "passive"))
      (node (ref "C16") (pin "1") (pinfunction "1_1") (pintype "passive"))
      (node (ref "C17") (pin "1") (pinfunction "1_1") (pintype "passive"))
      (node (ref "C18") (pin "2") (pinfunction "2_2") (pintype "passive"))
      (node (ref "C19") (pin "2") (pinfunction "2_2") (pintype "passive"))
      (node (ref "C2") (pin "1") (pinfunction "1_1") (pintype "passive"))
      (node (ref "C20") (pin "2") (pinfunction "2_2") (pintype "passive"))
      (node (ref "C21") (pin "1") (pinfunction "1_1") (pintype "passive"))
      (node (ref "C3") (pin "1") (pinfunction "1_1") (pintype "passive"))
      (node (ref "C4") (pin "1") (pinfunction "1_1") (pintype "passive"))
      (node (ref "C5") (pin "1") (pinfunction "1_1") (pintype "passive"))
      (node (ref "C6") (pin "1") (pinfunction "1_1") (pintype "passive"))
      (node (ref "C7") (pin "2") (pinfunction "2_2") (pintype "passive"))
      (node (ref "C8") (pin "1") (pinfunction "1_1") (pintype "passive"))
      (node (ref "C9") (pin "2") (pinfunction "2_2") (pintype "passive"))
      (node (ref "DS3232") (pin "10") (pinfunction "N.C._10") (pintype "passive"))
      (node (ref "DS3232") (pin "11") (pinfunction "N.C._11") (pintype "passive"))
      (node (ref "DS3232") (pin "12") (pinfunction "N.C._12") (pintype "passive"))
      (node (ref "DS3232") (pin "13") (pinfunction "GND_13") (pintype "passive"))
      (node (ref "DS3232") (pin "5") (pinfunction "N.C._5") (pintype "passive"))
      (node (ref "DS3232") (pin "6") (pinfunction "N.C._6") (pintype "passive"))
      (node (ref "DS3232") (pin "7") (pinfunction "N.C._7") (pintype "passive"))
      (node (ref "DS3232") (pin "8") (pinfunction "N.C._8") (pintype "passive"))
      (node (ref "DS3232") (pin "9") (pinfunction "N.C._9") (pintype "passive"))
      (node (ref "DUAL_NCH_1") (pin "1") (pinfunction "S1_1") (pintype "passive"))
      (node (ref "DUAL_NCH_1") (pin "3") (pinfunction "S2_3") (pintype "passive"))
      (node (ref "DUAL_NCH_2") (pin "1") (pinfunction "S1_1") (pintype "passive"))
      (node (ref "DUAL_NCH_2") (pin "3") (pinfunction "S2_3") (pintype "passive"))
      (node (ref "FRAM") (pin "4") (pinfunction "VSS_4") (pintype "passive"))
      (node (ref "INV_") (pin "3") (pinfunction "GND_3") (pintype "passive"))
      (node (ref "JST_BAT1") (pin "1") (pinfunction "GND_1") (pintype "passive"))
      (node (ref "JTAG") (pin "10") (pinfunction "10_10") (pintype "passive"))
      (node (ref "JTAG") (pin "2") (pinfunction "2_2") (pintype "passive"))
      (node (ref "K30_*") (pin "7") (pinfunction "G0_7") (pintype "passive"))
      (node (ref "MAIN_PWR_EN_OVRD") (pin "2") (pinfunction "2_2") (pintype "passive"))
      (node (ref "MCP73831") (pin "2") (pinfunction "VSS_2") (pintype "passive"))
      (node (ref "MCU_PWR") (pin "2") (pinfunction "K_2") (pintype "passive"))
      (node (ref "MEGA32U4") (pin "15") (pinfunction "GND_15") (pintype "passive"))
      (node (ref "MEGA32U4") (pin "23") (pinfunction "GND_23") (pintype "passive"))
      (node (ref "MEGA32U4") (pin "35") (pinfunction "GND_35") (pintype "passive"))
      (node (ref "MEGA32U4") (pin "43") (pinfunction "GND_43") (pintype "passive"))
      (node (ref "MEGA32U4") (pin "5") (pinfunction "UGnd_5") (pintype "passive"))
      (node (ref "R11") (pin "1") (pinfunction "1_1") (pintype "passive"))
      (node (ref "R12") (pin "1") (pinfunction "1_1") (pintype "passive"))
      (node (ref "R15") (pin "1") (pinfunction "1_1") (pintype "passive"))
      (node (ref "R17") (pin "2") (pinfunction "2_2") (pintype "passive"))
      (node (ref "R25") (pin "1") (pinfunction "1_1") (pintype "passive"))
      (node (ref "R27") (pin "1") (pinfunction "1_1") (pintype "passive"))
      (node (ref "R6") (pin "1") (pinfunction "1_1") (pintype "passive"))
      (node (ref "R7") (pin "1") (pinfunction "1_1") (pintype "passive"))
      (node (ref "R8") (pin "1") (pinfunction "1_1") (pintype "passive"))
      (node (ref "RESET_SU") (pin "2") (pinfunction "2_2") (pintype "passive"))
      (node (ref "RTC_RESET_1") (pin "1") (pinfunction "1_1") (pintype "passive"))
      (node (ref "TPS62742") (pin "3") (pinfunction "GND_3") (pintype "passive"))
      (node (ref "TPS63002_") (pin "3") (pinfunction "PGND_3") (pintype "passive"))
      (node (ref "TPS63002_") (pin "7") (pinfunction "PS/SYNC_7") (pintype "passive"))
      (node (ref "TPS63002_") (pin "9") (pinfunction "GND_9") (pintype "passive"))
      (node (ref "WAKE") (pin "1") (pinfunction "1_1") (pintype "passive"))
      (node (ref "XB24_SU") (pin "1") (pinfunction "GND_1") (pintype "passive"))
      (node (ref "XB24_SU") (pin "11") (pinfunction "GND_11") (pintype "passive"))
      (node (ref "XB24_SU") (pin "13") (pinfunction "GND_13") (pintype "passive"))
      (node (ref "XB24_SU") (pin "22") (pinfunction "GND_22") (pintype "passive"))
      (node (ref "XB24_SU") (pin "35") (pinfunction "GND_35") (pintype "passive"))
      (node (ref "uUSB_1") (pin "5") (pinfunction "GND_5") (pintype "passive"))
    )
    (net (code "36") (name "Net-(D3-K)") (class "Default")
      (node (ref "D3") (pin "2") (pinfunction "K_2") (pintype "passive"))
      (node (ref "R4") (pin "1") (pinfunction "1_1") (pintype "passive"))
    )
    (net (code "37") (name "Net-(DS3232-RST)") (class "Default")
      (node (ref "DS3232") (pin "4") (pinfunction "RST_4") (pintype "passive"))
      (node (ref "RTC_RESET_1") (pin "2") (pinfunction "2_2") (pintype "passive"))
    )
    (net (code "38") (name "Net-(DUAL_NCH_1-G1)") (class "Default")
      (node (ref "DUAL_NCH_1") (pin "2") (pinfunction "G1_2") (pintype "passive"))
      (node (ref "R12") (pin "2") (pinfunction "2_2") (pintype "passive"))
      (node (ref "USB_PWR_ON") (pin "2") (pinfunction "2_2") (pintype "passive"))
    )
    (net (code "39") (name "Net-(DUAL_NCH_2-G1)") (class "Default")
      (node (ref "DUAL_NCH_2") (pin "2") (pinfunction "G1_2") (pintype "passive"))
      (node (ref "R24") (pin "1") (pinfunction "1_1") (pintype "passive"))
      (node (ref "R25") (pin "2") (pinfunction "2_2") (pintype "passive"))
    )
    (net (code "40") (name "Net-(DUAL_NCH_2-G2)") (class "Default")
      (node (ref "DUAL_NCH_2") (pin "4") (pinfunction "G2_4") (pintype "passive"))
      (node (ref "R26") (pin "1") (pinfunction "1_1") (pintype "passive"))
      (node (ref "R27") (pin "2") (pinfunction "2_2") (pintype "passive"))
    )
    (net (code "41") (name "Net-(DUAL_RG_LED1-G_AN+)") (class "Default")
      (node (ref "DUAL_RG_LED1") (pin "1") (pinfunction "G_AN+_1") (pintype "passive"))
      (node (ref "R20") (pin "1") (pinfunction "1_1") (pintype "passive"))
    )
    (net (code "42") (name "Net-(DUAL_RG_LED1-G_CAT)") (class "Default")
      (node (ref "DUAL_NCH_2") (pin "5") (pinfunction "D2_5") (pintype "passive"))
      (node (ref "DUAL_NCH_2") (pin "6") (pinfunction "D2_6") (pintype "passive"))
      (node (ref "DUAL_RG_LED1") (pin "2") (pinfunction "G_CAT_2") (pintype "passive"))
    )
    (net (code "43") (name "Net-(DUAL_RG_LED1-R_AN)") (class "Default")
      (node (ref "DUAL_RG_LED1") (pin "3") (pinfunction "R_AN_3") (pintype "passive"))
      (node (ref "R22") (pin "1") (pinfunction "1_1") (pintype "passive"))
    )
    (net (code "44") (name "Net-(DUAL_RG_LED1-R_CAT)") (class "Default")
      (node (ref "DUAL_NCH_2") (pin "7") (pinfunction "D1_7") (pintype "passive"))
      (node (ref "DUAL_NCH_2") (pin "8") (pinfunction "D1_8") (pintype "passive"))
      (node (ref "DUAL_RG_LED1") (pin "4") (pinfunction "R_CAT_4") (pintype "passive"))
    )
    (net (code "45") (name "Net-(FRAM-A0)") (class "Default")
      (node (ref "FRAM") (pin "1") (pinfunction "A0_1") (pintype "passive"))
      (node (ref "R13") (pin "1") (pinfunction "1_1") (pintype "passive"))
    )
    (net (code "46") (name "Net-(K30_*-RX)") (class "Default")
      (node (ref "CO2_IO_EN") (pin "4") (pinfunction "4_4") (pintype "passive"))
      (node (ref "K30_*") (pin "5") (pinfunction "RX_5") (pintype "passive"))
    )
    (net (code "47") (name "Net-(K30_*-SCL)") (class "Default")
      (node (ref "CO2_IO_EN") (pin "8") (pinfunction "8_8") (pintype "passive"))
      (node (ref "K30_*") (pin "3") (pinfunction "SCL_3") (pintype "passive"))
    )
    (net (code "48") (name "Net-(K30_*-SDA)") (class "Default")
      (node (ref "CO2_IO_EN") (pin "6") (pinfunction "6_6") (pintype "passive"))
      (node (ref "K30_*") (pin "2") (pinfunction "SDA_2") (pintype "passive"))
    )
    (net (code "49") (name "Net-(K30_*-TX)") (class "Default")
      (node (ref "CO2_IO_EN") (pin "2") (pinfunction "2_2") (pintype "passive"))
      (node (ref "K30_*") (pin "4") (pinfunction "TX_4") (pintype "passive"))
    )
    (net (code "50") (name "Net-(MCP73831-PROG)") (class "Default")
      (node (ref "MCP73831") (pin "5") (pinfunction "PROG_5") (pintype "passive"))
      (node (ref "R8") (pin "2") (pinfunction "2_2") (pintype "passive"))
    )
    (net (code "51") (name "Net-(MCP73831-STAT)") (class "Default")
      (node (ref "MCP73831") (pin "1") (pinfunction "STAT_1") (pintype "passive"))
      (node (ref "R4") (pin "2") (pinfunction "2_2") (pintype "passive"))
    )
    (net (code "52") (name "Net-(MCU_PWR-A)") (class "Default")
      (node (ref "MCU_PWR") (pin "1") (pinfunction "A_1") (pintype "passive"))
      (node (ref "R10") (pin "2") (pinfunction "2_2") (pintype "passive"))
    )
    (net (code "53") (name "Net-(MEGA32U4-PE2_(~{HWB}))") (class "Default")
      (node (ref "MEGA32U4") (pin "33") (pinfunction "PE2_(~{HWB})_33") (pintype "passive"))
      (node (ref "R19") (pin "2") (pinfunction "2_2") (pintype "passive"))
    )
    (net (code "54") (name "Net-(MEGA32U4-XTAL1)") (class "Default")
      (node (ref "*") (pin "1") (pinfunction "1_1") (pintype "passive"))
      (node (ref "MEGA32U4") (pin "17") (pinfunction "XTAL1_17") (pintype "passive"))
    )
    (net (code "55") (name "Net-(MEGA32U4-XTAL2)") (class "Default")
      (node (ref "*") (pin "3") (pinfunction "3_3") (pintype "passive"))
      (node (ref "MEGA32U4") (pin "16") (pinfunction "XTAL2_16") (pintype "passive"))
    )
    (net (code "56") (name "Net-(R1-Pad1)") (class "Default")
      (node (ref "R1") (pin "1") (pinfunction "1_1") (pintype "passive"))
      (node (ref "R5") (pin "2") (pinfunction "2_2") (pintype "passive"))
      (node (ref "RESET_SU") (pin "1") (pinfunction "1_1") (pintype "passive"))
    )
    (net (code "57") (name "Net-(R16-Pad1)") (class "Default")
      (node (ref "R16") (pin "1") (pinfunction "1_1") (pintype "passive"))
      (node (ref "WAKE") (pin "2") (pinfunction "2_2") (pintype "passive"))
    )
    (net (code "58") (name "Net-(TPS62742-PG)") (class "Default")
      (node (ref "PWR_GOOD_MCU_RESET") (pin "1") (pinfunction "1_1") (pintype "passive"))
      (node (ref "R9") (pin "1") (pinfunction "1_1") (pintype "passive"))
      (node (ref "TPS62742") (pin "7") (pinfunction "PG_7") (pintype "passive"))
    )
    (net (code "59") (name "Net-(TPS62742-SW)") (class "Default")
      (node (ref "L1") (pin "1") (pinfunction "1_1") (pintype "passive"))
      (node (ref "TPS62742") (pin "2") (pinfunction "SW_2") (pintype "passive"))
    )
    (net (code "60") (name "Net-(TPS63002_-L1)") (class "Default")
      (node (ref "L2") (pin "1") (pinfunction "1_1") (pintype "passive"))
      (node (ref "TPS63002_") (pin "4") (pinfunction "L1_4") (pintype "passive"))
    )
    (net (code "61") (name "Net-(TPS63002_-L2)") (class "Default")
      (node (ref "L2") (pin "2") (pinfunction "2_2") (pintype "passive"))
      (node (ref "TPS63002_") (pin "2") (pinfunction "L2_2") (pintype "passive"))
    )
    (net (code "62") (name "Net-(TPS63002_-VINA)") (class "Default")
      (node (ref "C15") (pin "1") (pinfunction "1_1") (pintype "passive"))
      (node (ref "R18") (pin "2") (pinfunction "2_2") (pintype "passive"))
      (node (ref "TPS63002_") (pin "8") (pinfunction "VINA_8") (pintype "passive"))
    )
    (net (code "63") (name "unconnected-(DS3232-32kHz-Pad1)") (class "Default")
      (node (ref "DS3232") (pin "1") (pinfunction "32kHz_1") (pintype "passive"))
    )
    (net (code "64") (name "unconnected-(FRAM-A1-Pad2)") (class "Default")
      (node (ref "FRAM") (pin "2") (pinfunction "A1_2") (pintype "passive"))
    )
    (net (code "65") (name "unconnected-(FRAM-A2-Pad3)") (class "Default")
      (node (ref "FRAM") (pin "3") (pinfunction "A2_3") (pintype "passive"))
    )
    (net (code "66") (name "unconnected-(FRAM-WP-Pad7)") (class "Default")
      (node (ref "FRAM") (pin "7") (pinfunction "WP_7") (pintype "passive"))
    )
    (net (code "67") (name "unconnected-(INV_-N.C.-Pad1)") (class "Default")
      (node (ref "INV_") (pin "1") (pinfunction "N.C._1") (pintype "passive"))
    )
    (net (code "68") (name "unconnected-(JTAG-Pad7)") (class "Default")
      (node (ref "JTAG") (pin "7") (pinfunction "7_7") (pintype "passive"))
    )
    (net (code "69") (name "unconnected-(JTAG-Pad8)") (class "Default")
      (node (ref "JTAG") (pin "8") (pinfunction "8_8") (pintype "passive"))
    )
    (net (code "70") (name "unconnected-(K30_*-DVCC-Pad8)") (class "Default")
      (node (ref "K30_*") (pin "8") (pinfunction "DVCC_8") (pintype "passive"))
    )
    (net (code "71") (name "unconnected-(MEGA32U4-AREF-Pad42)") (class "Default")
      (node (ref "MEGA32U4") (pin "42") (pinfunction "AREF_42") (pintype "passive"))
    )
    (net (code "72") (name "unconnected-(MEGA32U4-PB0_(SS{slash}PCINT0)-Pad8)") (class "Default")
      (node (ref "MEGA32U4") (pin "8") (pinfunction "PB0_(SS/PCINT0)_8") (pintype "passive"))
    )
    (net (code "73") (name "unconnected-(MEGA32U4-PB1_(PCINT1{slash}SCLK)-Pad9)") (class "Default")
      (node (ref "MEGA32U4") (pin "9") (pinfunction "PB1_(PCINT1/SCLK)_9") (pintype "passive"))
    )
    (net (code "74") (name "unconnected-(MEGA32U4-PB2_(PDI{slash}PCINT2{slash}MOSI)-Pad10)") (class "Default")
      (node (ref "MEGA32U4") (pin "10") (pinfunction "PB2_(PDI/PCINT2/MOSI)_10") (pintype "passive"))
    )
    (net (code "75") (name "unconnected-(MEGA32U4-PB3_(PDO{slash}PCINT3{slash}MISO)-Pad11)") (class "Default")
      (node (ref "MEGA32U4") (pin "11") (pinfunction "PB3_(PDO/PCINT3/MISO)_11") (pintype "passive"))
    )
    (net (code "76") (name "unconnected-(MEGA32U4-PB5_(PCINT5{slash}OC1A{slash}~{OC4B}{slash}ADC12)-Pad29)") (class "Default")
      (node (ref "MEGA32U4") (pin "29") (pinfunction "PB5_(PCINT5/OC1A/~{OC4B}/ADC12)_29") (pintype "passive"))
    )
    (net (code "77") (name "unconnected-(MEGA32U4-UVcc-Pad2)") (class "Default")
      (node (ref "MEGA32U4") (pin "2") (pinfunction "UVcc_2") (pintype "passive"))
    )
    (net (code "78") (name "unconnected-(SW_-Pad3)") (class "Default")
      (node (ref "SW_") (pin "3") (pinfunction "3_3") (pintype "passive"))
    )
    (net (code "79") (name "unconnected-(XB24_SU-DIO0{slash}AD0-Pad33)") (class "Default")
      (node (ref "XB24_SU") (pin "33") (pinfunction "DIO0/AD0_33") (pintype "passive"))
    )
    (net (code "80") (name "unconnected-(XB24_SU-DIO1{slash}AD1-Pad32)") (class "Default")
      (node (ref "XB24_SU") (pin "32") (pinfunction "DIO1/AD1_32") (pintype "passive"))
    )
    (net (code "81") (name "unconnected-(XB24_SU-DIO2{slash}AD2-Pad31)") (class "Default")
      (node (ref "XB24_SU") (pin "31") (pinfunction "DIO2/AD2_31") (pintype "passive"))
    )
    (net (code "82") (name "unconnected-(XB24_SU-DIO3{slash}AD3-Pad30)") (class "Default")
      (node (ref "XB24_SU") (pin "30") (pinfunction "DIO3/AD3_30") (pintype "passive"))
    )
    (net (code "83") (name "unconnected-(XB24_SU-DIO4-Pad24)") (class "Default")
      (node (ref "XB24_SU") (pin "24") (pinfunction "DIO4_24") (pintype "passive"))
    )
    (net (code "84") (name "unconnected-(XB24_SU-DIO5{slash}ASSOC-Pad28)") (class "Default")
      (node (ref "XB24_SU") (pin "28") (pinfunction "DIO5/ASSOC_28") (pintype "passive"))
    )
    (net (code "85") (name "unconnected-(XB24_SU-DIO12-Pad5)") (class "Default")
      (node (ref "XB24_SU") (pin "5") (pinfunction "DIO12_5") (pintype "passive"))
    )
    (net (code "86") (name "unconnected-(XB24_SU-DOI11{slash}PWM1-Pad8)") (class "Default")
      (node (ref "XB24_SU") (pin "8") (pinfunction "DOI11/PWM1_8") (pintype "passive"))
    )
    (net (code "87") (name "unconnected-(XB24_SU-N.C.-Pad9)") (class "Default")
      (node (ref "XB24_SU") (pin "9") (pinfunction "N.C._9") (pintype "passive"))
    )
    (net (code "88") (name "unconnected-(XB24_SU-N.C.-Pad18)") (class "Default")
      (node (ref "XB24_SU") (pin "18") (pinfunction "N.C._18") (pintype "passive"))
    )
    (net (code "89") (name "unconnected-(XB24_SU-N.C.-Pad19)") (class "Default")
      (node (ref "XB24_SU") (pin "19") (pinfunction "N.C._19") (pintype "passive"))
    )
    (net (code "90") (name "unconnected-(XB24_SU-N.C.-Pad20)") (class "Default")
      (node (ref "XB24_SU") (pin "20") (pinfunction "N.C._20") (pintype "passive"))
    )
    (net (code "91") (name "unconnected-(XB24_SU-N.C.-Pad21)") (class "Default")
      (node (ref "XB24_SU") (pin "21") (pinfunction "N.C._21") (pintype "passive"))
    )
    (net (code "92") (name "unconnected-(XB24_SU-N.C.-Pad23)") (class "Default")
      (node (ref "XB24_SU") (pin "23") (pinfunction "N.C._23") (pintype "passive"))
    )
    (net (code "93") (name "unconnected-(XB24_SU-N.C.-Pad34)") (class "Default")
      (node (ref "XB24_SU") (pin "34") (pinfunction "N.C._34") (pintype "passive"))
    )
    (net (code "94") (name "unconnected-(XB24_SU-N.C.-Pad37)") (class "Default")
      (node (ref "XB24_SU") (pin "37") (pinfunction "N.C._37") (pintype "passive"))
    )
    (net (code "95") (name "unconnected-(XB24_SU-RF-Pad36)") (class "Default")
      (node (ref "XB24_SU") (pin "36") (pinfunction "RF_36") (pintype "passive"))
    )
    (net (code "96") (name "unconnected-(XB24_SU-SPI_CLK-Pad14)") (class "Default")
      (node (ref "XB24_SU") (pin "14") (pinfunction "SPI_CLK_14") (pintype "passive"))
    )
    (net (code "97") (name "unconnected-(XB24_SU-SPI_MISO-Pad17)") (class "Default")
      (node (ref "XB24_SU") (pin "17") (pinfunction "SPI_MISO_17") (pintype "passive"))
    )
    (net (code "98") (name "unconnected-(XB24_SU-SPI_MOSI-Pad16)") (class "Default")
      (node (ref "XB24_SU") (pin "16") (pinfunction "SPI_MOSI_16") (pintype "passive"))
    )
    (net (code "99") (name "unconnected-(XB24_SU-SPI_~{SSEL}-Pad15)") (class "Default")
      (node (ref "XB24_SU") (pin "15") (pinfunction "SPI_~{SSEL}_15") (pintype "passive"))
    )
    (net (code "100") (name "unconnected-(XB24_SU-VREF-Pad27)") (class "Default")
      (node (ref "XB24_SU") (pin "27") (pinfunction "VREF_27") (pintype "passive"))
    )
    (net (code "101") (name "unconnected-(XB24_SU-~{SPI_ATTN{slash}BOOTMODE}-Pad12)") (class "Default")
      (node (ref "XB24_SU") (pin "12") (pinfunction "~{SPI_ATTN/BOOTMODE}_12") (pintype "passive"))
    )
    (net (code "102") (name "unconnected-(uUSB_1-ID-Pad4)") (class "Default")
      (node (ref "uUSB_1") (pin "4") (pinfunction "ID_4") (pintype "passive"))
    )
  )
)
